# LED_Board.net
KiCad netlist of a schematic drawn in EAGLE
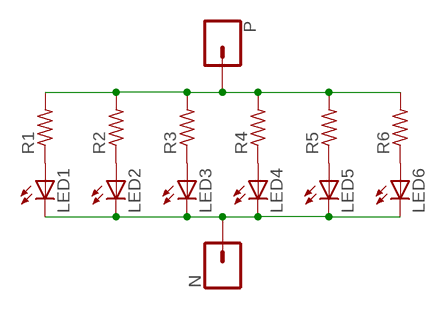
[diagram p0: schematic, sheet 1]

(export (version "E")
  (design (tool "Eeschema 10.0.6"))
  (components
    (comp (ref "LED1")
      (value "LEDCHIPLED_1206")
      (footprint "eagle-import:CHIPLED_1206")
      (libsource (lib "eagle-import") (part "LEDCHIPLED_1206"))
    )
    (comp (ref "LED2")
      (value "LEDCHIPLED_1206")
      (footprint "eagle-import:CHIPLED_1206")
      (libsource (lib "eagle-import") (part "LEDCHIPLED_1206"))
    )
    (comp (ref "LED3")
      (value "LEDCHIPLED_1206")
      (footprint "eagle-import:CHIPLED_1206")
      (libsource (lib "eagle-import") (part "LEDCHIPLED_1206"))
    )
    (comp (ref "LED4")
      (value "LEDCHIPLED_1206")
      (footprint "eagle-import:CHIPLED_1206")
      (libsource (lib "eagle-import") (part "LEDCHIPLED_1206"))
    )
    (comp (ref "LED5")
      (value "LEDCHIPLED_1206")
      (footprint "eagle-import:CHIPLED_1206")
      (libsource (lib "eagle-import") (part "LEDCHIPLED_1206"))
    )
    (comp (ref "LED6")
      (value "LEDCHIPLED_1206")
      (footprint "eagle-import:CHIPLED_1206")
      (libsource (lib "eagle-import") (part "LEDCHIPLED_1206"))
    )
    (comp (ref "N")
      (value "CONN_01")
      (footprint "eagle-import:1X01")
      (libsource (lib "eagle-import") (part "CONN_01"))
    )
    (comp (ref "P")
      (value "CONN_01")
      (footprint "eagle-import:1X01")
      (libsource (lib "eagle-import") (part "CONN_01"))
    )
    (comp (ref "R1")
      (value "R-US_M1206")
      (footprint "eagle-import:M1206")
      (libsource (lib "eagle-import") (part "R-US_M1206"))
    )
    (comp (ref "R2")
      (value "R-US_M1206")
      (footprint "eagle-import:M1206")
      (libsource (lib "eagle-import") (part "R-US_M1206"))
    )
    (comp (ref "R3")
      (value "R-US_M1206")
      (footprint "eagle-import:M1206")
      (libsource (lib "eagle-import") (part "R-US_M1206"))
    )
    (comp (ref "R4")
      (value "R-US_M1206")
      (footprint "eagle-import:M1206")
      (libsource (lib "eagle-import") (part "R-US_M1206"))
    )
    (comp (ref "R5")
      (value "R-US_M1206")
      (footprint "eagle-import:M1206")
      (libsource (lib "eagle-import") (part "R-US_M1206"))
    )
    (comp (ref "R6")
      (value "R-US_M1206")
      (footprint "eagle-import:M1206")
      (libsource (lib "eagle-import") (part "R-US_M1206"))
    )
  )
  (nets
    (net (code "1") (name "Net-(LED1-PadA)") (class "Default")
      (node (ref "LED1") (pin "A") (pinfunction "A_A") (pintype "passive"))
      (node (ref "R1") (pin "1") (pinfunction "1_1") (pintype "passive"))
    )
    (net (code "2") (name "Net-(LED1-PadC)") (class "Default")
      (node (ref "LED1") (pin "C") (pinfunction "C_C") (pintype "passive"))
      (node (ref "LED2") (pin "C") (pinfunction "C_C") (pintype "passive"))
      (node (ref "LED3") (pin "C") (pinfunction "C_C") (pintype "passive"))
      (node (ref "LED4") (pin "C") (pinfunction "C_C") (pintype "passive"))
      (node (ref "LED5") (pin "C") (pinfunction "C_C") (pintype "passive"))
      (node (ref "LED6") (pin "C") (pinfunction "C_C") (pintype "passive"))
      (node (ref "N") (pin "1") (pinfunction "1_1") (pintype "passive"))
    )
    (net (code "3") (name "Net-(LED2-PadA)") (class "Default")
      (node (ref "LED2") (pin "A") (pinfunction "A_A") (pintype "passive"))
      (node (ref "R2") (pin "1") (pinfunction "1_1") (pintype "passive"))
    )
    (net (code "4") (name "Net-(LED3-PadA)") (class "Default")
      (node (ref "LED3") (pin "A") (pinfunction "A_A") (pintype "passive"))
      (node (ref "R3") (pin "1") (pinfunction "1_1") (pintype "passive"))
    )
    (net (code "5") (name "Net-(LED4-PadA)") (class "Default")
      (node (ref "LED4") (pin "A") (pinfunction "A_A") (pintype "passive"))
      (node (ref "R4") (pin "1") (pinfunction "1_1") (pintype "passive"))
    )
    (net (code "6") (name "Net-(LED5-PadA)") (class "Default")
      (node (ref "LED5") (pin "A") (pinfunction "A_A") (pintype "passive"))
      (node (ref "R5") (pin "1") (pinfunction "1_1") (pintype "passive"))
    )
    (net (code "7") (name "Net-(LED6-PadA)") (class "Default")
      (node (ref "LED6") (pin "A") (pinfunction "A_A") (pintype "passive"))
      (node (ref "R6") (pin "1") (pinfunction "1_1") (pintype "passive"))
    )
    (net (code "8") (name "Net-(P-Pad1)") (class "Default")
      (node (ref "P") (pin "1") (pinfunction "1_1") (pintype "passive"))
      (node (ref "R1") (pin "2") (pinfunction "2_2") (pintype "passive"))
      (node (ref "R2") (pin "2") (pinfunction "2_2") (pintype "passive"))
      (node (ref "R3") (pin "2") (pinfunction "2_2") (pintype "passive"))
      (node (ref "R4") (pin "2") (pinfunction "2_2") (pintype "passive"))
      (node (ref "R5") (pin "2") (pinfunction "2_2") (pintype "passive"))
      (node (ref "R6") (pin "2") (pinfunction "2_2") (pintype "passive"))
    )
  )
)
